# electronics.net
KiCad netlist of a schematic drawn in EAGLE
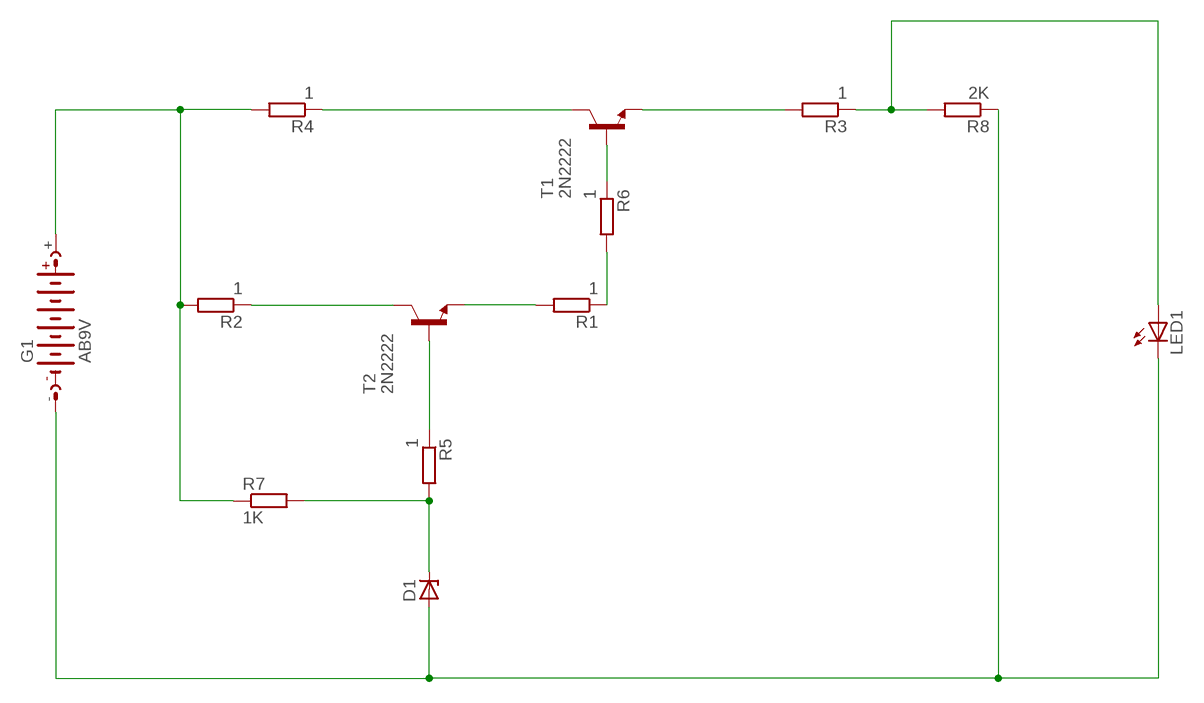
[diagram p0: schematic, sheet 1]

(export (version "E")
  (design (tool "Eeschema 10.0.6"))
  (components
    (comp (ref "D1")
      (value "ZENER-DIODEF126-12")
      (footprint "eagle-import:F126Z12")
      (libsource (lib "eagle-import") (part "ZENER-DIODEF126-12"))
    )
    (comp (ref "G1")
      (value "AB9V")
      (footprint "eagle-import:AB9V")
      (libsource (lib "eagle-import") (part "AB9V"))
    )
    (comp (ref "LED1")
      (value "LED5MM")
      (footprint "eagle-import:LED5MM")
      (libsource (lib "eagle-import") (part "LED5MM"))
    )
    (comp (ref "R1")
      (value "1")
      (footprint "eagle-import:0207_10")
      (libsource (lib "eagle-import") (part "R0207/10"))
    )
    (comp (ref "R2")
      (value "1")
      (footprint "eagle-import:0207_10")
      (libsource (lib "eagle-import") (part "R0207/10"))
    )
    (comp (ref "R3")
      (value "1")
      (footprint "eagle-import:0207_10")
      (libsource (lib "eagle-import") (part "R0207/10"))
    )
    (comp (ref "R4")
      (value "1")
      (footprint "eagle-import:0207_10")
      (libsource (lib "eagle-import") (part "R0207/10"))
    )
    (comp (ref "R5")
      (value "1")
      (footprint "eagle-import:0207_10")
      (libsource (lib "eagle-import") (part "R0207/10"))
    )
    (comp (ref "R6")
      (value "1")
      (footprint "eagle-import:0207_10")
      (libsource (lib "eagle-import") (part "R0207/10"))
    )
    (comp (ref "R7")
      (value "1K")
      (footprint "eagle-import:0207_10")
      (libsource (lib "eagle-import") (part "R0207/10"))
    )
    (comp (ref "R8")
      (value "2K")
      (footprint "eagle-import:0204_7")
      (libsource (lib "eagle-import") (part "R0204/7"))
    )
    (comp (ref "T1")
      (value "2N2222")
      (footprint "eagle-import:TO92-EBC-OVAL")
      (libsource (lib "eagle-import") (part "2N2222"))
    )
    (comp (ref "T2")
      (value "2N2222")
      (footprint "eagle-import:TO92-EBC-OVAL")
      (libsource (lib "eagle-import") (part "2N2222"))
    )
  )
  (nets
    (net (code "1") (name "Net-(D1-PadC)") (class "Default")
      (node (ref "D1") (pin "C") (pinfunction "C_C") (pintype "passive"))
      (node (ref "R5") (pin "2") (pinfunction "2_2") (pintype "passive"))
      (node (ref "R7") (pin "2") (pinfunction "2_2") (pintype "passive"))
    )
    (net (code "2") (name "Net-(G1-Pad+)") (class "Default")
      (node (ref "G1") (pin "+") (pinfunction "+_+") (pintype "passive"))
      (node (ref "R2") (pin "2") (pinfunction "2_2") (pintype "passive"))
      (node (ref "R4") (pin "2") (pinfunction "2_2") (pintype "passive"))
      (node (ref "R7") (pin "1") (pinfunction "1_1") (pintype "passive"))
    )
    (net (code "3") (name "Net-(LED1-C)") (class "Default")
      (node (ref "D1") (pin "A") (pinfunction "A_A") (pintype "passive"))
      (node (ref "G1") (pin "-") (pinfunction "-_-") (pintype "passive"))
      (node (ref "LED1") (pin "K") (pinfunction "C_K") (pintype "passive"))
      (node (ref "R8") (pin "1") (pinfunction "1_1") (pintype "passive"))
    )
    (net (code "4") (name "Net-(LED1-PadA)") (class "Default")
      (node (ref "LED1") (pin "A") (pinfunction "A_A") (pintype "passive"))
      (node (ref "R3") (pin "1") (pinfunction "1_1") (pintype "passive"))
      (node (ref "R8") (pin "2") (pinfunction "2_2") (pintype "passive"))
    )
    (net (code "5") (name "Net-(R1-Pad1)") (class "Default")
      (node (ref "R1") (pin "1") (pinfunction "1_1") (pintype "passive"))
      (node (ref "R6") (pin "2") (pinfunction "2_2") (pintype "passive"))
    )
    (net (code "6") (name "Net-(R1-Pad2)") (class "Default")
      (node (ref "R1") (pin "2") (pinfunction "2_2") (pintype "passive"))
      (node (ref "T2") (pin "E") (pinfunction "E_E") (pintype "passive"))
    )
    (net (code "7") (name "Net-(R2-Pad1)") (class "Default")
      (node (ref "R2") (pin "1") (pinfunction "1_1") (pintype "passive"))
      (node (ref "T2") (pin "C") (pinfunction "C_C") (pintype "passive"))
    )
    (net (code "8") (name "Net-(R3-Pad2)") (class "Default")
      (node (ref "R3") (pin "2") (pinfunction "2_2") (pintype "passive"))
      (node (ref "T1") (pin "E") (pinfunction "E_E") (pintype "passive"))
    )
    (net (code "9") (name "Net-(R4-Pad1)") (class "Default")
      (node (ref "R4") (pin "1") (pinfunction "1_1") (pintype "passive"))
      (node (ref "T1") (pin "C") (pinfunction "C_C") (pintype "passive"))
    )
    (net (code "10") (name "Net-(R5-Pad1)") (class "Default")
      (node (ref "R5") (pin "1") (pinfunction "1_1") (pintype "passive"))
      (node (ref "T2") (pin "B") (pinfunction "B_B") (pintype "passive"))
    )
    (net (code "11") (name "Net-(R6-Pad1)") (class "Default")
      (node (ref "R6") (pin "1") (pinfunction "1_1") (pintype "passive"))
      (node (ref "T1") (pin "B") (pinfunction "B_B") (pintype "passive"))
    )
  )
)
